# XMICRO-7SEG.net
KiCad netlist of a schematic drawn in EAGLE
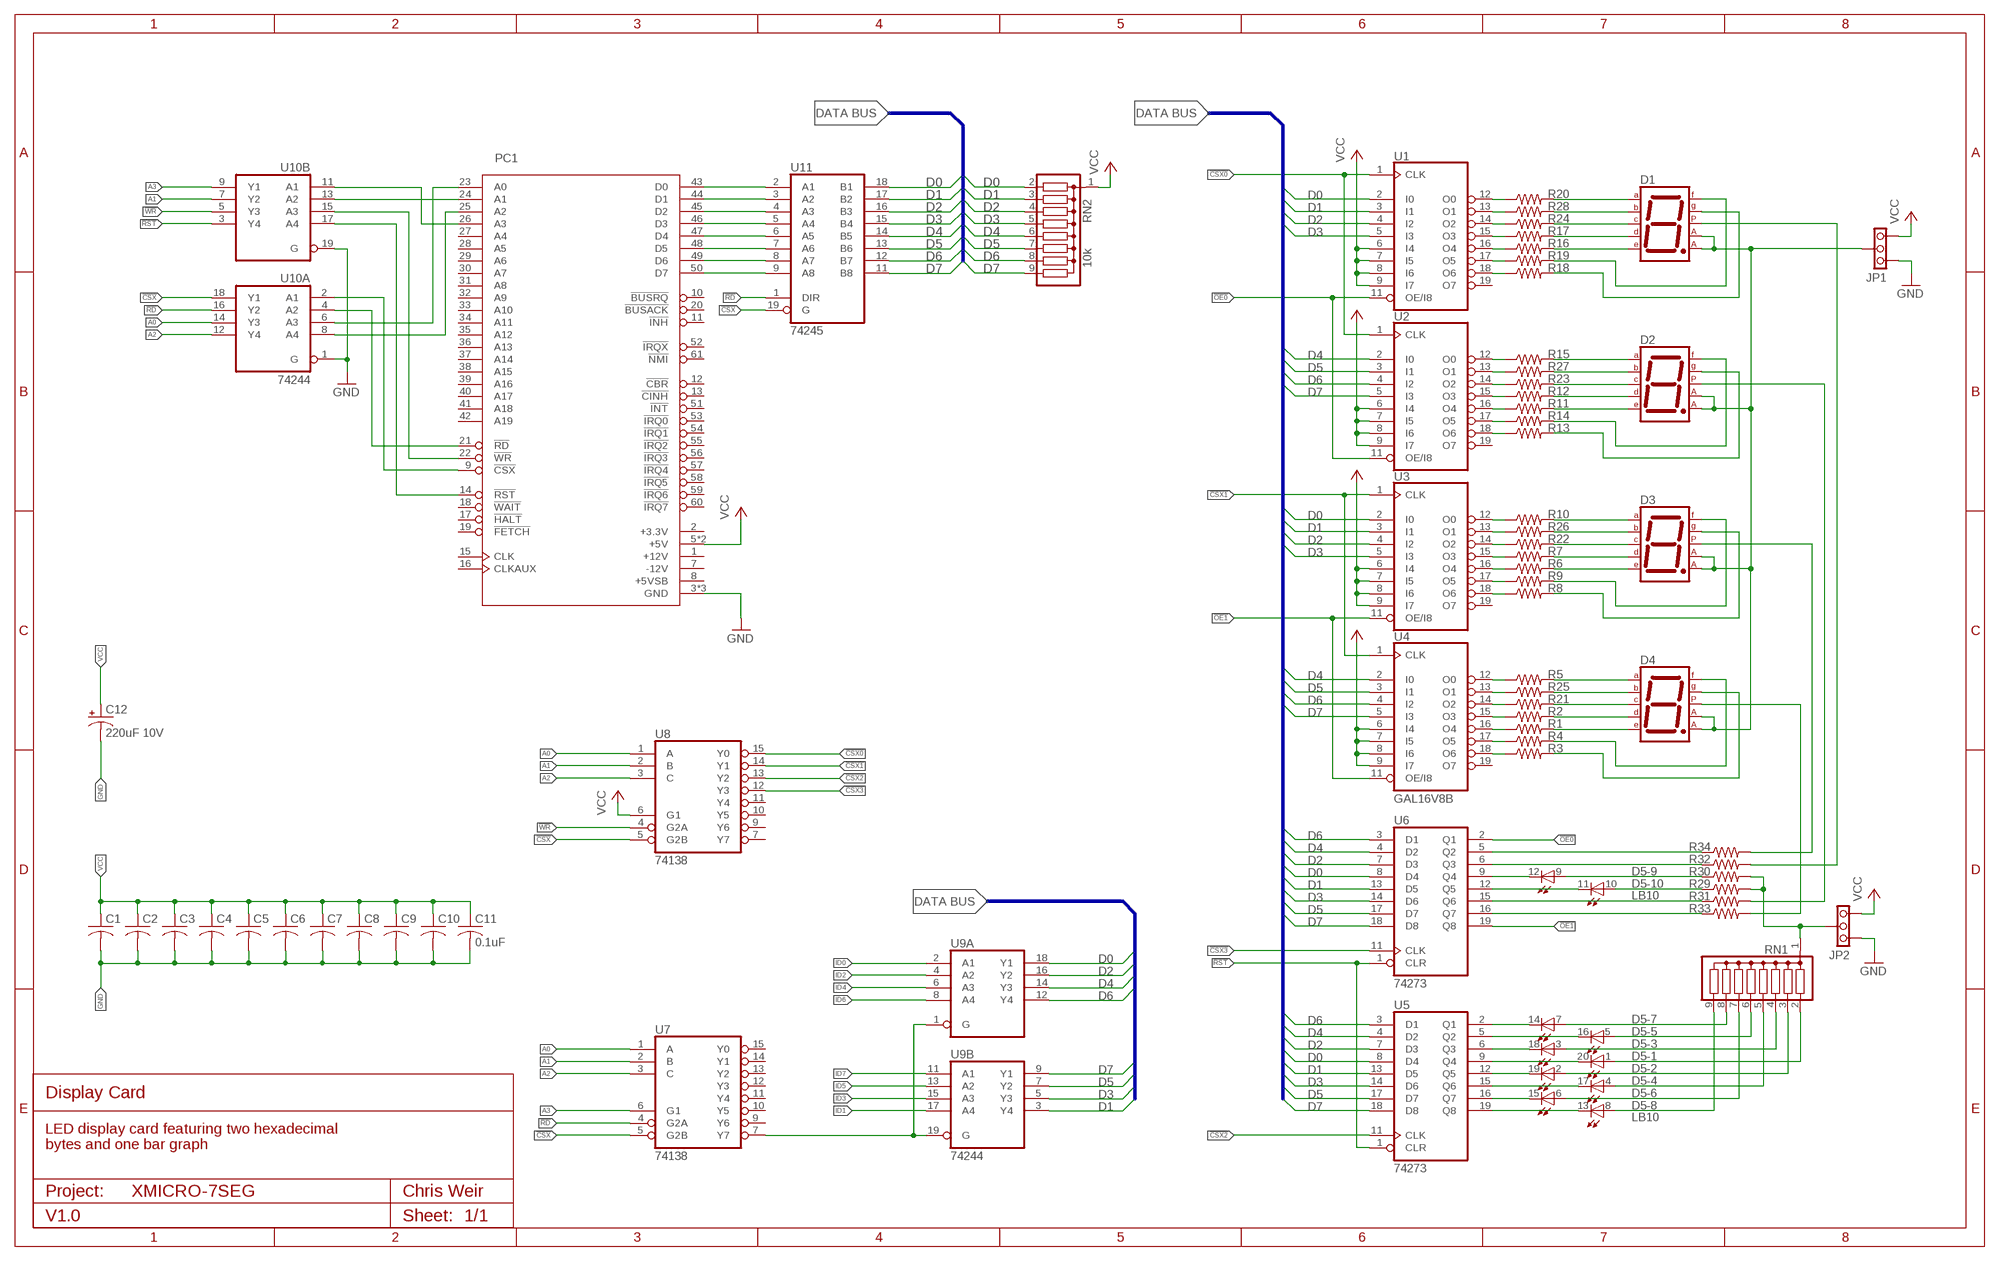
[diagram p0: schematic, sheet 1]

(export (version "E")
  (design (tool "Eeschema 10.0.6"))
  (components
    (comp (ref "C1")
      (value "0.1uF")
      (footprint "eagle-import:C025-024X044")
      (libsource (lib "eagle-import") (part "C-US025-024X044"))
    )
    (comp (ref "C2")
      (value "0.1uF")
      (footprint "eagle-import:C025-024X044")
      (libsource (lib "eagle-import") (part "C-US025-024X044"))
    )
    (comp (ref "C3")
      (value "0.1uF")
      (footprint "eagle-import:C025-024X044")
      (libsource (lib "eagle-import") (part "C-US025-024X044"))
    )
    (comp (ref "C4")
      (value "0.1uF")
      (footprint "eagle-import:C025-024X044")
      (libsource (lib "eagle-import") (part "C-US025-024X044"))
    )
    (comp (ref "C5")
      (value "0.1uF")
      (footprint "eagle-import:C025-024X044")
      (libsource (lib "eagle-import") (part "C-US025-024X044"))
    )
    (comp (ref "C6")
      (value "0.1uF")
      (footprint "eagle-import:C025-024X044")
      (libsource (lib "eagle-import") (part "C-US025-024X044"))
    )
    (comp (ref "C7")
      (value "0.1uF")
      (footprint "eagle-import:C025-024X044")
      (libsource (lib "eagle-import") (part "C-US025-024X044"))
    )
    (comp (ref "C8")
      (value "0.1uF")
      (footprint "eagle-import:C025-024X044")
      (libsource (lib "eagle-import") (part "C-US025-024X044"))
    )
    (comp (ref "C9")
      (value "0.1uF")
      (footprint "eagle-import:C025-024X044")
      (libsource (lib "eagle-import") (part "C-US025-024X044"))
    )
    (comp (ref "C10")
      (value "0.1uF")
      (footprint "eagle-import:C025-024X044")
      (libsource (lib "eagle-import") (part "C-US025-024X044"))
    )
    (comp (ref "C11")
      (value "0.1uF")
      (footprint "eagle-import:C025-024X044")
      (libsource (lib "eagle-import") (part "C-US025-024X044"))
    )
    (comp (ref "C12")
      (value "220uF 10V")
      (footprint "eagle-import:C-10-5")
      (libsource (lib "eagle-import") (part "CPOL-US-10-5"))
    )
    (comp (ref "D1")
      (value "7SEG-CA")
      (footprint "eagle-import:7SEG-13")
      (libsource (lib "eagle-import") (part "7SEG-CA"))
    )
    (comp (ref "D2")
      (value "7SEG-CA")
      (footprint "eagle-import:7SEG-13")
      (libsource (lib "eagle-import") (part "7SEG-CA"))
    )
    (comp (ref "D3")
      (value "7SEG-CA")
      (footprint "eagle-import:7SEG-13")
      (libsource (lib "eagle-import") (part "7SEG-CA"))
    )
    (comp (ref "D4")
      (value "7SEG-CA")
      (footprint "eagle-import:7SEG-13")
      (libsource (lib "eagle-import") (part "7SEG-CA"))
    )
    (comp (ref "D5")
      (value "LB10")
      (footprint "eagle-import:LB10")
      (libsource (lib "eagle-import") (part "LB10"))
    )
    (comp (ref "JP1")
      (value "PINHD1X3THRU")
      (footprint "eagle-import:1X03")
      (libsource (lib "eagle-import") (part "PINHD1X3THRU"))
    )
    (comp (ref "JP2")
      (value "PINHD1X3THRU")
      (footprint "eagle-import:1X03")
      (libsource (lib "eagle-import") (part "PINHD1X3THRU"))
    )
    (comp (ref "PC1")
      (value "XMICRO-BUS-EDGE62M")
      (footprint "eagle-import:EDGE62M")
      (libsource (lib "eagle-import") (part "XMICRO-BUS-EDGE62M"))
    )
    (comp (ref "R1")
      (value "R-US_0207/10")
      (footprint "eagle-import:0207_10")
      (libsource (lib "eagle-import") (part "R-US_0207/10"))
    )
    (comp (ref "R2")
      (value "R-US_0207/10")
      (footprint "eagle-import:0207_10")
      (libsource (lib "eagle-import") (part "R-US_0207/10"))
    )
    (comp (ref "R3")
      (value "R-US_0207/10")
      (footprint "eagle-import:0207_10")
      (libsource (lib "eagle-import") (part "R-US_0207/10"))
    )
    (comp (ref "R4")
      (value "R-US_0207/10")
      (footprint "eagle-import:0207_10")
      (libsource (lib "eagle-import") (part "R-US_0207/10"))
    )
    (comp (ref "R5")
      (value "R-US_0207/10")
      (footprint "eagle-import:0207_10")
      (libsource (lib "eagle-import") (part "R-US_0207/10"))
    )
    (comp (ref "R6")
      (value "R-US_0207/10")
      (footprint "eagle-import:0207_10")
      (libsource (lib "eagle-import") (part "R-US_0207/10"))
    )
    (comp (ref "R7")
      (value "R-US_0207/10")
      (footprint "eagle-import:0207_10")
      (libsource (lib "eagle-import") (part "R-US_0207/10"))
    )
    (comp (ref "R8")
      (value "R-US_0207/10")
      (footprint "eagle-import:0207_10")
      (libsource (lib "eagle-import") (part "R-US_0207/10"))
    )
    (comp (ref "R9")
      (value "R-US_0207/10")
      (footprint "eagle-import:0207_10")
      (libsource (lib "eagle-import") (part "R-US_0207/10"))
    )
    (comp (ref "R10")
      (value "R-US_0207/10")
      (footprint "eagle-import:0207_10")
      (libsource (lib "eagle-import") (part "R-US_0207/10"))
    )
    (comp (ref "R11")
      (value "R-US_0207/10")
      (footprint "eagle-import:0207_10")
      (libsource (lib "eagle-import") (part "R-US_0207/10"))
    )
    (comp (ref "R12")
      (value "R-US_0207/10")
      (footprint "eagle-import:0207_10")
      (libsource (lib "eagle-import") (part "R-US_0207/10"))
    )
    (comp (ref "R13")
      (value "R-US_0207/10")
      (footprint "eagle-import:0207_10")
      (libsource (lib "eagle-import") (part "R-US_0207/10"))
    )
    (comp (ref "R14")
      (value "R-US_0207/10")
      (footprint "eagle-import:0207_10")
      (libsource (lib "eagle-import") (part "R-US_0207/10"))
    )
    (comp (ref "R15")
      (value "R-US_0207/10")
      (footprint "eagle-import:0207_10")
      (libsource (lib "eagle-import") (part "R-US_0207/10"))
    )
    (comp (ref "R16")
      (value "R-US_0207/10")
      (footprint "eagle-import:0207_10")
      (libsource (lib "eagle-import") (part "R-US_0207/10"))
    )
    (comp (ref "R17")
      (value "R-US_0207/10")
      (footprint "eagle-import:0207_10")
      (libsource (lib "eagle-import") (part "R-US_0207/10"))
    )
    (comp (ref "R18")
      (value "R-US_0207/10")
      (footprint "eagle-import:0207_10")
      (libsource (lib "eagle-import") (part "R-US_0207/10"))
    )
    (comp (ref "R19")
      (value "R-US_0207/10")
      (footprint "eagle-import:0207_10")
      (libsource (lib "eagle-import") (part "R-US_0207/10"))
    )
    (comp (ref "R20")
      (value "R-US_0207/10")
      (footprint "eagle-import:0207_10")
      (libsource (lib "eagle-import") (part "R-US_0207/10"))
    )
    (comp (ref "R21")
      (value "R-US_0207/10")
      (footprint "eagle-import:0207_10")
      (libsource (lib "eagle-import") (part "R-US_0207/10"))
    )
    (comp (ref "R22")
      (value "R-US_0207/10")
      (footprint "eagle-import:0207_10")
      (libsource (lib "eagle-import") (part "R-US_0207/10"))
    )
    (comp (ref "R23")
      (value "R-US_0207/10")
      (footprint "eagle-import:0207_10")
      (libsource (lib "eagle-import") (part "R-US_0207/10"))
    )
    (comp (ref "R24")
      (value "R-US_0207/10")
      (footprint "eagle-import:0207_10")
      (libsource (lib "eagle-import") (part "R-US_0207/10"))
    )
    (comp (ref "R25")
      (value "R-US_0207/10")
      (footprint "eagle-import:0207_10")
      (libsource (lib "eagle-import") (part "R-US_0207/10"))
    )
    (comp (ref "R26")
      (value "R-US_0207/10")
      (footprint "eagle-import:0207_10")
      (libsource (lib "eagle-import") (part "R-US_0207/10"))
    )
    (comp (ref "R27")
      (value "R-US_0207/10")
      (footprint "eagle-import:0207_10")
      (libsource (lib "eagle-import") (part "R-US_0207/10"))
    )
    (comp (ref "R28")
      (value "R-US_0207/10")
      (footprint "eagle-import:0207_10")
      (libsource (lib "eagle-import") (part "R-US_0207/10"))
    )
    (comp (ref "R29")
      (value "R-US_0207/10")
      (footprint "eagle-import:0207_10")
      (libsource (lib "eagle-import") (part "R-US_0207/10"))
    )
    (comp (ref "R30")
      (value "R-US_0207/10")
      (footprint "eagle-import:0207_10")
      (libsource (lib "eagle-import") (part "R-US_0207/10"))
    )
    (comp (ref "R31")
      (value "R-US_0207/10")
      (footprint "eagle-import:0207_10")
      (libsource (lib "eagle-import") (part "R-US_0207/10"))
    )
    (comp (ref "R32")
      (value "R-US_0207/10")
      (footprint "eagle-import:0207_10")
      (libsource (lib "eagle-import") (part "R-US_0207/10"))
    )
    (comp (ref "R33")
      (value "R-US_0207/10")
      (footprint "eagle-import:0207_10")
      (libsource (lib "eagle-import") (part "R-US_0207/10"))
    )
    (comp (ref "R34")
      (value "R-US_0207/10")
      (footprint "eagle-import:0207_10")
      (libsource (lib "eagle-import") (part "R-US_0207/10"))
    )
    (comp (ref "RN1")
      (value "G08R")
      (footprint "eagle-import:SIL9")
      (libsource (lib "eagle-import") (part "G08R"))
    )
    (comp (ref "RN2")
      (value "10k")
      (footprint "eagle-import:SIL9")
      (fields (field (name "OC_FARNELL") "unknown") (field (name "OC_NEWARK") "unknown"))
      (libsource (lib "eagle-import") (part "G08R"))
    )
    (comp (ref "U1")
      (value "GAL16V8B")
      (footprint "eagle-import:DIL20")
      (fields (field (name "MPN") "GAL16V8D-7LPN"))
      (libsource (lib "eagle-import") (part "16V8"))
    )
    (comp (ref "U2")
      (value "GAL16V8B")
      (footprint "eagle-import:DIL20")
      (fields (field (name "MPN") "GAL16V8D-7LPN"))
      (libsource (lib "eagle-import") (part "16V8"))
    )
    (comp (ref "U3")
      (value "GAL16V8B")
      (footprint "eagle-import:DIL20")
      (fields (field (name "MPN") "GAL16V8D-7LPN"))
      (libsource (lib "eagle-import") (part "16V8"))
    )
    (comp (ref "U4")
      (value "GAL16V8B")
      (footprint "eagle-import:DIL20")
      (fields (field (name "MPN") "GAL16V8D-7LPN"))
      (libsource (lib "eagle-import") (part "16V8"))
    )
    (comp (ref "U5")
      (value "74273")
      (footprint "eagle-import:DIL20")
      (libsource (lib "eagle-import") (part "74273N"))
    )
    (comp (ref "U6")
      (value "74273")
      (footprint "eagle-import:DIL20")
      (libsource (lib "eagle-import") (part "74273N"))
    )
    (comp (ref "U7")
      (value "74138")
      (footprint "eagle-import:DIL16")
      (libsource (lib "eagle-import") (part "74138NLS"))
    )
    (comp (ref "U8")
      (value "74138")
      (footprint "eagle-import:DIL16")
      (libsource (lib "eagle-import") (part "74138NLS"))
    )
    (comp (ref "U9")
      (value "74244")
      (footprint "eagle-import:DIL20")
      (libsource (lib "eagle-import") (part "74244NLS"))
    )
    (comp (ref "U10")
      (value "74244")
      (footprint "eagle-import:DIL20")
      (libsource (lib "eagle-import") (part "74244NLS"))
    )
    (comp (ref "U11")
      (value "74245")
      (footprint "eagle-import:DIL20")
      (libsource (lib "eagle-import") (part "74245NLS"))
    )
  )
  (nets
    (net (code "1") (name "/D0") (class "Default")
      (node (ref "RN2") (pin "2") (pinfunction "2_2") (pintype "passive"))
      (node (ref "U1") (pin "2") (pinfunction "I0_2") (pintype "input"))
      (node (ref "U11") (pin "18") (pinfunction "B1_18") (pintype "bidirectional"))
      (node (ref "U3") (pin "2") (pinfunction "I0_2") (pintype "input"))
      (node (ref "U5") (pin "8") (pinfunction "D4_8") (pintype "input"))
      (node (ref "U6") (pin "8") (pinfunction "D4_8") (pintype "input"))
      (node (ref "U9") (pin "18") (pinfunction "Y1_18") (pintype "tri_state"))
    )
    (net (code "2") (name "/D1") (class "Default")
      (node (ref "RN2") (pin "3") (pinfunction "3_3") (pintype "passive"))
      (node (ref "U1") (pin "3") (pinfunction "I1_3") (pintype "input"))
      (node (ref "U11") (pin "17") (pinfunction "B2_17") (pintype "bidirectional"))
      (node (ref "U3") (pin "3") (pinfunction "I1_3") (pintype "input"))
      (node (ref "U5") (pin "13") (pinfunction "D5_13") (pintype "input"))
      (node (ref "U6") (pin "13") (pinfunction "D5_13") (pintype "input"))
      (node (ref "U9") (pin "3") (pinfunction "Y4_3") (pintype "tri_state"))
    )
    (net (code "3") (name "/D2") (class "Default")
      (node (ref "RN2") (pin "4") (pinfunction "4_4") (pintype "passive"))
      (node (ref "U1") (pin "4") (pinfunction "I2_4") (pintype "input"))
      (node (ref "U11") (pin "16") (pinfunction "B3_16") (pintype "bidirectional"))
      (node (ref "U3") (pin "4") (pinfunction "I2_4") (pintype "input"))
      (node (ref "U5") (pin "7") (pinfunction "D3_7") (pintype "input"))
      (node (ref "U6") (pin "7") (pinfunction "D3_7") (pintype "input"))
      (node (ref "U9") (pin "16") (pinfunction "Y2_16") (pintype "tri_state"))
    )
    (net (code "4") (name "/D3") (class "Default")
      (node (ref "RN2") (pin "5") (pinfunction "5_5") (pintype "passive"))
      (node (ref "U1") (pin "5") (pinfunction "I3_5") (pintype "input"))
      (node (ref "U11") (pin "15") (pinfunction "B4_15") (pintype "bidirectional"))
      (node (ref "U3") (pin "5") (pinfunction "I3_5") (pintype "input"))
      (node (ref "U5") (pin "14") (pinfunction "D6_14") (pintype "input"))
      (node (ref "U6") (pin "14") (pinfunction "D6_14") (pintype "input"))
      (node (ref "U9") (pin "5") (pinfunction "Y3_5") (pintype "tri_state"))
    )
    (net (code "5") (name "/D4") (class "Default")
      (node (ref "RN2") (pin "6") (pinfunction "6_6") (pintype "passive"))
      (node (ref "U11") (pin "14") (pinfunction "B5_14") (pintype "bidirectional"))
      (node (ref "U2") (pin "2") (pinfunction "I0_2") (pintype "input"))
      (node (ref "U4") (pin "2") (pinfunction "I0_2") (pintype "input"))
      (node (ref "U5") (pin "4") (pinfunction "D2_4") (pintype "input"))
      (node (ref "U6") (pin "4") (pinfunction "D2_4") (pintype "input"))
      (node (ref "U9") (pin "14") (pinfunction "Y3_14") (pintype "tri_state"))
    )
    (net (code "6") (name "/D5") (class "Default")
      (node (ref "RN2") (pin "7") (pinfunction "7_7") (pintype "passive"))
      (node (ref "U11") (pin "13") (pinfunction "B6_13") (pintype "bidirectional"))
      (node (ref "U2") (pin "3") (pinfunction "I1_3") (pintype "input"))
      (node (ref "U4") (pin "3") (pinfunction "I1_3") (pintype "input"))
      (node (ref "U5") (pin "17") (pinfunction "D7_17") (pintype "input"))
      (node (ref "U6") (pin "17") (pinfunction "D7_17") (pintype "input"))
      (node (ref "U9") (pin "7") (pinfunction "Y2_7") (pintype "tri_state"))
    )
    (net (code "7") (name "/D6") (class "Default")
      (node (ref "RN2") (pin "8") (pinfunction "8_8") (pintype "passive"))
      (node (ref "U11") (pin "12") (pinfunction "B7_12") (pintype "bidirectional"))
      (node (ref "U2") (pin "4") (pinfunction "I2_4") (pintype "input"))
      (node (ref "U4") (pin "4") (pinfunction "I2_4") (pintype "input"))
      (node (ref "U5") (pin "3") (pinfunction "D1_3") (pintype "input"))
      (node (ref "U6") (pin "3") (pinfunction "D1_3") (pintype "input"))
      (node (ref "U9") (pin "12") (pinfunction "Y4_12") (pintype "tri_state"))
    )
    (net (code "8") (name "/D7") (class "Default")
      (node (ref "RN2") (pin "9") (pinfunction "9_9") (pintype "passive"))
      (node (ref "U11") (pin "11") (pinfunction "B8_11") (pintype "bidirectional"))
      (node (ref "U2") (pin "5") (pinfunction "I3_5") (pintype "input"))
      (node (ref "U4") (pin "5") (pinfunction "I3_5") (pintype "input"))
      (node (ref "U5") (pin "18") (pinfunction "D8_18") (pintype "input"))
      (node (ref "U6") (pin "18") (pinfunction "D8_18") (pintype "input"))
      (node (ref "U9") (pin "9") (pinfunction "Y1_9") (pintype "tri_state"))
    )
    (net (code "10") (name "/~{CSX0}") (class "Default")
      (node (ref "U1") (pin "1") (pinfunction "CLK_1") (pintype "input"))
      (node (ref "U2") (pin "1") (pinfunction "CLK_1") (pintype "input"))
      (node (ref "U8") (pin "15") (pinfunction "Y0_15") (pintype "output"))
    )
    (net (code "11") (name "/~{CSX1}") (class "Default")
      (node (ref "U3") (pin "1") (pinfunction "CLK_1") (pintype "input"))
      (node (ref "U4") (pin "1") (pinfunction "CLK_1") (pintype "input"))
      (node (ref "U8") (pin "14") (pinfunction "Y1_14") (pintype "output"))
    )
    (net (code "12") (name "/~{CSX2}") (class "Default")
      (node (ref "U5") (pin "11") (pinfunction "CLK_11") (pintype "input"))
      (node (ref "U8") (pin "13") (pinfunction "Y2_13") (pintype "output"))
    )
    (net (code "13") (name "/~{CSX3}") (class "Default")
      (node (ref "U6") (pin "11") (pinfunction "CLK_11") (pintype "input"))
      (node (ref "U8") (pin "12") (pinfunction "Y3_12") (pintype "output"))
    )
    (net (code "14") (name "/~{CSX}") (class "Default")
      (node (ref "U10") (pin "18") (pinfunction "Y1_18") (pintype "tri_state"))
      (node (ref "U11") (pin "19") (pinfunction "G_19") (pintype "input"))
      (node (ref "U7") (pin "5") (pinfunction "G2B_5") (pintype "input"))
      (node (ref "U8") (pin "5") (pinfunction "G2B_5") (pintype "input"))
    )
    (net (code "15") (name "/~{OE0}") (class "Default")
      (node (ref "U1") (pin "11") (pinfunction "OE/I8_11") (pintype "input"))
      (node (ref "U2") (pin "11") (pinfunction "OE/I8_11") (pintype "input"))
      (node (ref "U6") (pin "2") (pinfunction "Q1_2") (pintype "output"))
    )
    (net (code "16") (name "/~{OE1}") (class "Default")
      (node (ref "U3") (pin "11") (pinfunction "OE/I8_11") (pintype "input"))
      (node (ref "U4") (pin "11") (pinfunction "OE/I8_11") (pintype "input"))
      (node (ref "U6") (pin "19") (pinfunction "Q8_19") (pintype "output"))
    )
    (net (code "17") (name "/~{RD}") (class "Default")
      (node (ref "U10") (pin "16") (pinfunction "Y2_16") (pintype "tri_state"))
      (node (ref "U11") (pin "1") (pinfunction "DIR_1") (pintype "input"))
      (node (ref "U7") (pin "4") (pinfunction "G2A_4") (pintype "input"))
    )
    (net (code "18") (name "/~{RST}") (class "Default")
      (node (ref "U10") (pin "3") (pinfunction "Y4_3") (pintype "tri_state"))
      (node (ref "U5") (pin "1") (pinfunction "CLR_1") (pintype "input"))
      (node (ref "U6") (pin "1") (pinfunction "CLR_1") (pintype "input"))
    )
    (net (code "19") (name "/~{WR}") (class "Default")
      (node (ref "U10") (pin "5") (pinfunction "Y3_5") (pintype "tri_state"))
      (node (ref "U8") (pin "4") (pinfunction "G2A_4") (pintype "input"))
    )
    (net (code "20") (name "A0") (class "Default")
      (node (ref "U10") (pin "14") (pinfunction "Y3_14") (pintype "tri_state"))
      (node (ref "U7") (pin "1") (pinfunction "A_1") (pintype "input"))
      (node (ref "U8") (pin "1") (pinfunction "A_1") (pintype "input"))
    )
    (net (code "21") (name "A1") (class "Default")
      (node (ref "U10") (pin "7") (pinfunction "Y2_7") (pintype "tri_state"))
      (node (ref "U7") (pin "2") (pinfunction "B_2") (pintype "input"))
      (node (ref "U8") (pin "2") (pinfunction "B_2") (pintype "input"))
    )
    (net (code "22") (name "A2") (class "Default")
      (node (ref "U10") (pin "12") (pinfunction "Y4_12") (pintype "tri_state"))
      (node (ref "U7") (pin "3") (pinfunction "C_3") (pintype "input"))
      (node (ref "U8") (pin "3") (pinfunction "C_3") (pintype "input"))
    )
    (net (code "23") (name "A3") (class "Default")
      (node (ref "U10") (pin "9") (pinfunction "Y1_9") (pintype "tri_state"))
      (node (ref "U7") (pin "6") (pinfunction "G1_6") (pintype "input"))
    )
    (net (code "24") (name "GND") (class "Default")
      (node (ref "C1") (pin "2") (pinfunction "2_2") (pintype "passive"))
      (node (ref "C10") (pin "2") (pinfunction "2_2") (pintype "passive"))
      (node (ref "C11") (pin "2") (pinfunction "2_2") (pintype "passive"))
      (node (ref "C12") (pin "-") (pinfunction "-_-") (pintype "passive"))
      (node (ref "C2") (pin "2") (pinfunction "2_2") (pintype "passive"))
      (node (ref "C3") (pin "2") (pinfunction "2_2") (pintype "passive"))
      (node (ref "C4") (pin "2") (pinfunction "2_2") (pintype "passive"))
      (node (ref "C5") (pin "2") (pinfunction "2_2") (pintype "passive"))
      (node (ref "C6") (pin "2") (pinfunction "2_2") (pintype "passive"))
      (node (ref "C7") (pin "2") (pinfunction "2_2") (pintype "passive"))
      (node (ref "C8") (pin "2") (pinfunction "2_2") (pintype "passive"))
      (node (ref "C9") (pin "2") (pinfunction "2_2") (pintype "passive"))
      (node (ref "JP1") (pin "1") (pinfunction "1_1") (pintype "passive"))
      (node (ref "JP2") (pin "1") (pinfunction "1_1") (pintype "passive"))
      (node (ref "PC1") (pin "3") (pinfunction "GND_3") (pintype "bidirectional"))
      (node (ref "PC1") (pin "4") (pinfunction "GND_4") (pintype "bidirectional"))
      (node (ref "PC1") (pin "62") (pinfunction "GND_62") (pintype "bidirectional"))
      (node (ref "U10") (pin "1") (pinfunction "G_1") (pintype "input"))
      (node (ref "U10") (pin "19") (pinfunction "G_19") (pintype "input"))
    )
    (net (code "25") (name "ID0") (class "Default")
      (node (ref "U9") (pin "2") (pinfunction "A1_2") (pintype "input"))
    )
    (net (code "26") (name "ID1") (class "Default")
      (node (ref "U9") (pin "17") (pinfunction "A4_17") (pintype "input"))
    )
    (net (code "27") (name "ID2") (class "Default")
      (node (ref "U9") (pin "4") (pinfunction "A2_4") (pintype "input"))
    )
    (net (code "28") (name "ID3") (class "Default")
      (node (ref "U9") (pin "15") (pinfunction "A3_15") (pintype "input"))
    )
    (net (code "29") (name "ID4") (class "Default")
      (node (ref "U9") (pin "6") (pinfunction "A3_6") (pintype "input"))
    )
    (net (code "30") (name "ID5") (class "Default")
      (node (ref "U9") (pin "13") (pinfunction "A2_13") (pintype "input"))
    )
    (net (code "31") (name "ID6") (class "Default")
      (node (ref "U9") (pin "8") (pinfunction "A4_8") (pintype "input"))
    )
    (net (code "32") (name "ID7") (class "Default")
      (node (ref "U9") (pin "11") (pinfunction "A1_11") (pintype "input"))
    )
    (net (code "33") (name "Net-(D1-A)") (class "Default")
      (node (ref "D1") (pin "7") (pinfunction "A_7") (pintype "passive"))
      (node (ref "R20") (pin "2") (pinfunction "2_2") (pintype "passive"))
    )
    (net (code "34") (name "Net-(D1-B)") (class "Default")
      (node (ref "D1") (pin "6") (pinfunction "B_6") (pintype "passive"))
      (node (ref "R28") (pin "2") (pinfunction "2_2") (pintype "passive"))
    )
    (net (code "35") (name "Net-(D1-C)") (class "Default")
      (node (ref "D1") (pin "4") (pinfunction "C_4") (pintype "passive"))
      (node (ref "R24") (pin "2") (pinfunction "2_2") (pintype "passive"))
    )
    (net (code "36") (name "Net-(D1-CA1)") (class "Default")
      (node (ref "D1") (pin "3") (pinfunction "CA1_3") (pintype "passive"))
      (node (ref "D1") (pin "8") (pinfunction "CA2_8") (pintype "passive"))
      (node (ref "D2") (pin "3") (pinfunction "CA1_3") (pintype "passive"))
      (node (ref "D2") (pin "8") (pinfunction "CA2_8") (pintype "passive"))
      (node (ref "D3") (pin "3") (pinfunction "CA1_3") (pintype "passive"))
      (node (ref "D3") (pin "8") (pinfunction "CA2_8") (pintype "passive"))
      (node (ref "D4") (pin "3") (pinfunction "CA1_3") (pintype "passive"))
      (node (ref "D4") (pin "8") (pinfunction "CA2_8") (pintype "passive"))
      (node (ref "JP1") (pin "2") (pinfunction "2_2") (pintype "passive"))
    )
    (net (code "37") (name "Net-(D1-D)") (class "Default")
      (node (ref "D1") (pin "2") (pinfunction "D_2") (pintype "passive"))
      (node (ref "R17") (pin "2") (pinfunction "2_2") (pintype "passive"))
    )
    (net (code "38") (name "Net-(D1-DP)") (class "Default")
      (node (ref "D1") (pin "5") (pinfunction "DP_5") (pintype "passive"))
      (node (ref "R32") (pin "2") (pinfunction "2_2") (pintype "passive"))
    )
    (net (code "39") (name "Net-(D1-E)") (class "Default")
      (node (ref "D1") (pin "1") (pinfunction "E_1") (pintype "passive"))
      (node (ref "R16") (pin "2") (pinfunction "2_2") (pintype "passive"))
    )
    (net (code "40") (name "Net-(D1-F)") (class "Default")
      (node (ref "D1") (pin "9") (pinfunction "F_9") (pintype "passive"))
      (node (ref "R19") (pin "2") (pinfunction "2_2") (pintype "passive"))
    )
    (net (code "41") (name "Net-(D1-G)") (class "Default")
      (node (ref "D1") (pin "10") (pinfunction "G_10") (pintype "passive"))
      (node (ref "R18") (pin "2") (pinfunction "2_2") (pintype "passive"))
    )
    (net (code "42") (name "Net-(D2-A)") (class "Default")
      (node (ref "D2") (pin "7") (pinfunction "A_7") (pintype "passive"))
      (node (ref "R15") (pin "2") (pinfunction "2_2") (pintype "passive"))
    )
    (net (code "43") (name "Net-(D2-B)") (class "Default")
      (node (ref "D2") (pin "6") (pinfunction "B_6") (pintype "passive"))
      (node (ref "R27") (pin "2") (pinfunction "2_2") (pintype "passive"))
    )
    (net (code "44") (name "Net-(D2-C)") (class "Default")
      (node (ref "D2") (pin "4") (pinfunction "C_4") (pintype "passive"))
      (node (ref "R23") (pin "2") (pinfunction "2_2") (pintype "passive"))
    )
    (net (code "45") (name "Net-(D2-D)") (class "Default")
      (node (ref "D2") (pin "2") (pinfunction "D_2") (pintype "passive"))
      (node (ref "R12") (pin "2") (pinfunction "2_2") (pintype "passive"))
    )
    (net (code "46") (name "Net-(D2-DP)") (class "Default")
      (node (ref "D2") (pin "5") (pinfunction "DP_5") (pintype "passive"))
      (node (ref "R31") (pin "2") (pinfunction "2_2") (pintype "passive"))
    )
    (net (code "47") (name "Net-(D2-E)") (class "Default")
      (node (ref "D2") (pin "1") (pinfunction "E_1") (pintype "passive"))
      (node (ref "R11") (pin "2") (pinfunction "2_2") (pintype "passive"))
    )
    (net (code "48") (name "Net-(D2-F)") (class "Default")
      (node (ref "D2") (pin "9") (pinfunction "F_9") (pintype "passive"))
      (node (ref "R14") (pin "2") (pinfunction "2_2") (pintype "passive"))
    )
    (net (code "49") (name "Net-(D2-G)") (class "Default")
      (node (ref "D2") (pin "10") (pinfunction "G_10") (pintype "passive"))
      (node (ref "R13") (pin "2") (pinfunction "2_2") (pintype "passive"))
    )
    (net (code "50") (name "Net-(D3-A)") (class "Default")
      (node (ref "D3") (pin "7") (pinfunction "A_7") (pintype "passive"))
      (node (ref "R10") (pin "2") (pinfunction "2_2") (pintype "passive"))
    )
    (net (code "51") (name "Net-(D3-B)") (class "Default")
      (node (ref "D3") (pin "6") (pinfunction "B_6") (pintype "passive"))
      (node (ref "R26") (pin "2") (pinfunction "2_2") (pintype "passive"))
    )
    (net (code "52") (name "Net-(D3-C)") (class "Default")
      (node (ref "D3") (pin "4") (pinfunction "C_4") (pintype "passive"))
      (node (ref "R22") (pin "2") (pinfunction "2_2") (pintype "passive"))
    )
    (net (code "53") (name "Net-(D3-D)") (class "Default")
      (node (ref "D3") (pin "2") (pinfunction "D_2") (pintype "passive"))
      (node (ref "R7") (pin "2") (pinfunction "2_2") (pintype "passive"))
    )
    (net (code "54") (name "Net-(D3-DP)") (class "Default")
      (node (ref "D3") (pin "5") (pinfunction "DP_5") (pintype "passive"))
      (node (ref "R34") (pin "2") (pinfunction "2_2") (pintype "passive"))
    )
    (net (code "55") (name "Net-(D3-E)") (class "Default")
      (node (ref "D3") (pin "1") (pinfunction "E_1") (pintype "passive"))
      (node (ref "R6") (pin "2") (pinfunction "2_2") (pintype "passive"))
    )
    (net (code "56") (name "Net-(D3-F)") (class "Default")
      (node (ref "D3") (pin "9") (pinfunction "F_9") (pintype "passive"))
      (node (ref "R9") (pin "2") (pinfunction "2_2") (pintype "passive"))
    )
    (net (code "57") (name "Net-(D3-G)") (class "Default")
      (node (ref "D3") (pin "10") (pinfunction "G_10") (pintype "passive"))
      (node (ref "R8") (pin "2") (pinfunction "2_2") (pintype "passive"))
    )
    (net (code "58") (name "Net-(D4-A)") (class "Default")
      (node (ref "D4") (pin "7") (pinfunction "A_7") (pintype "passive"))
      (node (ref "R5") (pin "2") (pinfunction "2_2") (pintype "passive"))
    )
    (net (code "59") (name "Net-(D4-B)") (class "Default")
      (node (ref "D4") (pin "6") (pinfunction "B_6") (pintype "passive"))
      (node (ref "R25") (pin "2") (pinfunction "2_2") (pintype "passive"))
    )
    (net (code "60") (name "Net-(D4-C)") (class "Default")
      (node (ref "D4") (pin "4") (pinfunction "C_4") (pintype "passive"))
      (node (ref "R21") (pin "2") (pinfunction "2_2") (pintype "passive"))
    )
    (net (code "61") (name "Net-(D4-D)") (class "Default")
      (node (ref "D4") (pin "2") (pinfunction "D_2") (pintype "passive"))
      (node (ref "R2") (pin "2") (pinfunction "2_2") (pintype "passive"))
    )
    (net (code "62") (name "Net-(D4-DP)") (class "Default")
      (node (ref "D4") (pin "5") (pinfunction "DP_5") (pintype "passive"))
      (node (ref "R33") (pin "2") (pinfunction "2_2") (pintype "passive"))
    )
    (net (code "63") (name "Net-(D4-E)") (class "Default")
      (node (ref "D4") (pin "1") (pinfunction "E_1") (pintype "passive"))
      (node (ref "R1") (pin "2") (pinfunction "2_2") (pintype "passive"))
    )
    (net (code "64") (name "Net-(D4-F)") (class "Default")
      (node (ref "D4") (pin "9") (pinfunction "F_9") (pintype "passive"))
      (node (ref "R4") (pin "2") (pinfunction "2_2") (pintype "passive"))
    )
    (net (code "65") (name "Net-(D4-G)") (class "Default")
      (node (ref "D4") (pin "10") (pinfunction "G_10") (pintype "passive"))
      (node (ref "R3") (pin "2") (pinfunction "2_2") (pintype "passive"))
    )
    (net (code "66") (name "Net-(D5A-A)") (class "Default")
      (node (ref "D5") (pin "1") (pinfunction "A_1") (pintype "passive"))
      (node (ref "RN1") (pin "2") (pinfunction "2_2") (pintype "passive"))
    )
    (net (code "67") (name "Net-(D5A-C)") (class "Default")
      (node (ref "D5") (pin "20") (pinfunction "C_20") (pintype "passive"))
      (node (ref "U5") (pin "9") (pinfunction "Q4_9") (pintype "output"))
    )
    (net (code "68") (name "Net-(D5B-A)") (class "Default")
      (node (ref "D5") (pin "10") (pinfunction "A_10") (pintype "passive"))
      (node (ref "R29") (pin "1") (pinfunction "1_1") (pintype "passive"))
    )
    (net (code "69") (name "Net-(D5B-C)") (class "Default")
      (node (ref "D5") (pin "11") (pinfunction "C_11") (pintype "passive"))
      (node (ref "U6") (pin "12") (pinfunction "Q5_12") (pintype "output"))
    )
    (net (code "70") (name "Net-(D5C-A)") (class "Default")
      (node (ref "D5") (pin "2") (pinfunction "A_2") (pintype "passive"))
      (node (ref "RN1") (pin "3") (pinfunction "3_3") (pintype "passive"))
    )
    (net (code "71") (name "Net-(D5C-C)") (class "Default")
      (node (ref "D5") (pin "19") (pinfunction "C_19") (pintype "passive"))
      (node (ref "U5") (pin "12") (pinfunction "Q5_12") (pintype "output"))
    )
    (net (code "72") (name "Net-(D5D-A)") (class "Default")
      (node (ref "D5") (pin "3") (pinfunction "A_3") (pintype "passive"))
      (node (ref "RN1") (pin "4") (pinfunction "4_4") (pintype "passive"))
    )
    (net (code "73") (name "Net-(D5D-C)") (class "Default")
      (node (ref "D5") (pin "18") (pinfunction "C_18") (pintype "passive"))
      (node (ref "U5") (pin "6") (pinfunction "Q3_6") (pintype "output"))
    )
    (net (code "74") (name "Net-(D5E-A)") (class "Default")
      (node (ref "D5") (pin "4") (pinfunction "A_4") (pintype "passive"))
      (node (ref "RN1") (pin "5") (pinfunction "5_5") (pintype "passive"))
    )
    (net (code "75") (name "Net-(D5E-C)") (class "Default")
      (node (ref "D5") (pin "17") (pinfunction "C_17") (pintype "passive"))
      (node (ref "U5") (pin "15") (pinfunction "Q6_15") (pintype "output"))
    )
    (net (code "76") (name "Net-(D5F-A)") (class "Default")
      (node (ref "D5") (pin "5") (pinfunction "A_5") (pintype "passive"))
      (node (ref "RN1") (pin "6") (pinfunction "6_6") (pintype "passive"))
    )
    (net (code "77") (name "Net-(D5F-C)") (class "Default")
      (node (ref "D5") (pin "16") (pinfunction "C_16") (pintype "passive"))
      (node (ref "U5") (pin "5") (pinfunction "Q2_5") (pintype "output"))
    )
    (net (code "78") (name "Net-(D5G-A)") (class "Default")
      (node (ref "D5") (pin "6") (pinfunction "A_6") (pintype "passive"))
      (node (ref "RN1") (pin "7") (pinfunction "7_7") (pintype "passive"))
    )
    (net (code "79") (name "Net-(D5G-C)") (class "Default")
      (node (ref "D5") (pin "15") (pinfunction "C_15") (pintype "passive"))
      (node (ref "U5") (pin "16") (pinfunction "Q7_16") (pintype "output"))
    )
    (net (code "80") (name "Net-(D5H-A)") (class "Default")
      (node (ref "D5") (pin "7") (pinfunction "A_7") (pintype "passive"))
      (node (ref "RN1") (pin "8") (pinfunction "8_8") (pintype "passive"))
    )
    (net (code "81") (name "Net-(D5H-C)") (class "Default")
      (node (ref "D5") (pin "14") (pinfunction "C_14") (pintype "passive"))
      (node (ref "U5") (pin "2") (pinfunction "Q1_2") (pintype "output"))
    )
    (net (code "82") (name "Net-(D5I-A)") (class "Default")
      (node (ref "D5") (pin "8") (pinfunction "A_8") (pintype "passive"))
      (node (ref "RN1") (pin "9") (pinfunction "9_9") (pintype "passive"))
    )
    (net (code "83") (name "Net-(D5I-C)") (class "Default")
      (node (ref "D5") (pin "13") (pinfunction "C_13") (pintype "passive"))
      (node (ref "U5") (pin "19") (pinfunction "Q8_19") (pintype "output"))
    )
    (net (code "84") (name "Net-(D5J-A)") (class "Default")
      (node (ref "D5") (pin "9") (pinfunction "A_9") (pintype "passive"))
      (node (ref "R30") (pin "1") (pinfunction "1_1") (pintype "passive"))
    )
    (net (code "85") (name "Net-(D5J-C)") (class "Default")
      (node (ref "D5") (pin "12") (pinfunction "C_12") (pintype "passive"))
      (node (ref "U6") (pin "9") (pinfunction "Q4_9") (pintype "output"))
    )
    (net (code "86") (name "Net-(JP2-Pad2)") (class "Default")
      (node (ref "JP2") (pin "2") (pinfunction "2_2") (pintype "passive"))
      (node (ref "R29") (pin "2") (pinfunction "2_2") (pintype "passive"))
      (node (ref "R30") (pin "2") (pinfunction "2_2") (pintype "passive"))
      (node (ref "RN1") (pin "1") (pinfunction "1_1") (pintype "passive"))
    )
    (net (code "87") (name "Net-(PC1-A0)") (class "Default")
      (node (ref "PC1") (pin "23") (pinfunction "A0_23") (pintype "bidirectional"))
      (node (ref "U10") (pin "6") (pinfunction "A3_6") (pintype "input"))
    )
    (net (code "88") (name "Net-(PC1-A1)") (class "Default")
      (node (ref "PC1") (pin "24") (pinfunction "A1_24") (pintype "bidirectional"))
      (node (ref "U10") (pin "13") (pinfunction "A2_13") (pintype "input"))
    )
    (net (code "89") (name "Net-(PC1-A2)") (class "Default")
      (node (ref "PC1") (pin "25") (pinfunction "A2_25") (pintype "bidirectional"))
      (node (ref "U10") (pin "8") (pinfunction "A4_8") (pintype "input"))
    )
    (net (code "90") (name "Net-(PC1-A3)") (class "Default")
      (node (ref "PC1") (pin "26") (pinfunction "A3_26") (pintype "bidirectional"))
      (node (ref "U10") (pin "11") (pinfunction "A1_11") (pintype "input"))
    )
    (net (code "91") (name "Net-(PC1-D0)") (class "Default")
      (node (ref "PC1") (pin "43") (pinfunction "D0_43") (pintype "bidirectional"))
      (node (ref "U11") (pin "2") (pinfunction "A1_2") (pintype "bidirectional"))
    )
    (net (code "92") (name "Net-(PC1-D1)") (class "Default")
      (node (ref "PC1") (pin "44") (pinfunction "D1_44") (pintype "bidirectional"))
      (node (ref "U11") (pin "3") (pinfunction "A2_3") (pintype "bidirectional"))
    )
    (net (code "93") (name "Net-(PC1-D2)") (class "Default")
      (node (ref "PC1") (pin "45") (pinfunction "D2_45") (pintype "bidirectional"))
      (node (ref "U11") (pin "4") (pinfunction "A3_4") (pintype "bidirectional"))
    )
    (net (code "94") (name "Net-(PC1-D3)") (class "Default")
      (node (ref "PC1") (pin "46") (pinfunction "D3_46") (pintype "bidirectional"))
      (node (ref "U11") (pin "5") (pinfunction "A4_5") (pintype "bidirectional"))
    )
    (net (code "95") (name "Net-(PC1-D4)") (class "Default")
      (node (ref "PC1") (pin "47") (pinfunction "D4_47") (pintype "bidirectional"))
      (node (ref "U11") (pin "6") (pinfunction "A5_6") (pintype "bidirectional"))
    )
    (net (code "96") (name "Net-(PC1-D5)") (class "Default")
      (node (ref "PC1") (pin "48") (pinfunction "D5_48") (pintype "bidirectional"))
      (node (ref "U11") (pin "7") (pinfunction "A6_7") (pintype "bidirectional"))
    )
    (net (code "97") (name "Net-(PC1-D6)") (class "Default")
      (node (ref "PC1") (pin "49") (pinfunction "D6_49") (pintype "bidirectional"))
      (node (ref "U11") (pin "8") (pinfunction "A7_8") (pintype "bidirectional"))
    )
    (net (code "98") (name "Net-(PC1-D7)") (class "Default")
      (node (ref "PC1") (pin "50") (pinfunction "D7_50") (pintype "bidirectional"))
      (node (ref "U11") (pin "9") (pinfunction "A8_9") (pintype "bidirectional"))
    )
    (net (code "99") (name "Net-(PC1-~{CSX})") (class "Default")
      (node (ref "PC1") (pin "9") (pinfunction "~{CSX}_9") (pintype "bidirectional"))
      (node (ref "U10") (pin "2") (pinfunction "A1_2") (pintype "input"))
    )
    (net (code "100") (name "Net-(PC1-~{RD})") (class "Default")
      (node (ref "PC1") (pin "21") (pinfunction "~{RD}_21") (pintype "bidirectional"))
      (node (ref "U10") (pin "4") (pinfunction "A2_4") (pintype "input"))
    )
    (net (code "101") (name "Net-(PC1-~{RST})") (class "Default")
      (node (ref "PC1") (pin "14") (pinfunction "~{RST}_14") (pintype "bidirectional"))
      (node (ref "U10") (pin "17") (pinfunction "A4_17") (pintype "input"))
    )
    (net (code "102") (name "Net-(PC1-~{WR})") (class "Default")
      (node (ref "PC1") (pin "22") (pinfunction "~{WR}_22") (pintype "bidirectional"))
      (node (ref "U10") (pin "15") (pinfunction "A3_15") (pintype "input"))
    )
    (net (code "103") (name "Net-(U1A-O0)") (class "Default")
      (node (ref "R20") (pin "1") (pinfunction "1_1") (pintype "passive"))
      (node (ref "U1") (pin "12") (pinfunction "O0_12") (pintype "bidirectional"))
    )
    (net (code "104") (name "Net-(U1A-O1)") (class "Default")
      (node (ref "R28") (pin "1") (pinfunction "1_1") (pintype "passive"))
      (node (ref "U1") (pin "13") (pinfunction "O1_13") (pintype "bidirectional"))
    )
    (net (code "105") (name "Net-(U1A-O2)") (class "Default")
      (node (ref "R24") (pin "1") (pinfunction "1_1") (pintype "passive"))
      (node (ref "U1") (pin "14") (pinfunction "O2_14") (pintype "bidirectional"))
    )
    (net (code "106") (name "Net-(U1A-O3)") (class "Default")
      (node (ref "R17") (pin "1") (pinfunction "1_1") (pintype "passive"))
      (node (ref "U1") (pin "15") (pinfunction "O3_15") (pintype "bidirectional"))
    )
    (net (code "107") (name "Net-(U1A-O4)") (class "Default")
      (node (ref "R16") (pin "1") (pinfunction "1_1") (pintype "passive"))
      (node (ref "U1") (pin "16") (pinfunction "O4_16") (pintype "bidirectional"))
    )
    (net (code "108") (name "Net-(U1A-O5)") (class "Default")
      (node (ref "R19") (pin "1") (pinfunction "1_1") (pintype "passive"))
      (node (ref "U1") (pin "17") (pinfunction "O5_17") (pintype "bidirectional"))
    )
    (net (code "109") (name "Net-(U1A-O6)") (class "Default")
      (node (ref "R18") (pin "1") (pinfunction "1_1") (pintype "passive"))
      (node (ref "U1") (pin "18") (pinfunction "O6_18") (pintype "bidirectional"))
    )
    (net (code "110") (name "Net-(U2A-O0)") (class "Default")
      (node (ref "R15") (pin "1") (pinfunction "1_1") (pintype "passive"))
      (node (ref "U2") (pin "12") (pinfunction "O0_12") (pintype "bidirectional"))
    )
    (net (code "111") (name "Net-(U2A-O1)") (class "Default")
      (node (ref "R27") (pin "1") (pinfunction "1_1") (pintype "passive"))
      (node (ref "U2") (pin "13") (pinfunction "O1_13") (pintype "bidirectional"))
    )
    (net (code "112") (name "Net-(U2A-O2)") (class "Default")
      (node (ref "R23") (pin "1") (pinfunction "1_1") (pintype "passive"))
      (node (ref "U2") (pin "14") (pinfunction "O2_14") (pintype "bidirectional"))
    )
    (net (code "113") (name "Net-(U2A-O3)") (class "Default")
      (node (ref "R12") (pin "1") (pinfunction "1_1") (pintype "passive"))
      (node (ref "U2") (pin "15") (pinfunction "O3_15") (pintype "bidirectional"))
    )
    (net (code "114") (name "Net-(U2A-O4)") (class "Default")
      (node (ref "R11") (pin "1") (pinfunction "1_1") (pintype "passive"))
      (node (ref "U2") (pin "16") (pinfunction "O4_16") (pintype "bidirectional"))
    )
    (net (code "115") (name "Net-(U2A-O5)") (class "Default")
      (node (ref "R14") (pin "1") (pinfunction "1_1") (pintype "passive"))
      (node (ref "U2") (pin "17") (pinfunction "O5_17") (pintype "bidirectional"))
    )
    (net (code "116") (name "Net-(U2A-O6)") (class "Default")
      (node (ref "R13") (pin "1") (pinfunction "1_1") (pintype "passive"))
      (node (ref "U2") (pin "18") (pinfunction "O6_18") (pintype "bidirectional"))
    )
    (net (code "117") (name "Net-(U3A-O0)") (class "Default")
      (node (ref "R10") (pin "1") (pinfunction "1_1") (pintype "passive"))
      (node (ref "U3") (pin "12") (pinfunction "O0_12") (pintype "bidirectional"))
    )
    (net (code "118") (name "Net-(U3A-O1)") (class "Default")
      (node (ref "R26") (pin "1") (pinfunction "1_1") (pintype "passive"))
      (node (ref "U3") (pin "13") (pinfunction "O1_13") (pintype "bidirectional"))
    )
    (net (code "119") (name "Net-(U3A-O2)") (class "Default")
      (node (ref "R22") (pin "1") (pinfunction "1_1") (pintype "passive"))
      (node (ref "U3") (pin "14") (pinfunction "O2_14") (pintype "bidirectional"))
    )
    (net (code "120") (name "Net-(U3A-O3)") (class "Default")
      (node (ref "R7") (pin "1") (pinfunction "1_1") (pintype "passive"))
      (node (ref "U3") (pin "15") (pinfunction "O3_15") (pintype "bidirectional"))
    )
    (net (code "121") (name "Net-(U3A-O4)") (class "Default")
      (node (ref "R6") (pin "1") (pinfunction "1_1") (pintype "passive"))
      (node (ref "U3") (pin "16") (pinfunction "O4_16") (pintype "bidirectional"))
    )
    (net (code "122") (name "Net-(U3A-O5)") (class "Default")
      (node (ref "R9") (pin "1") (pinfunction "1_1") (pintype "passive"))
      (node (ref "U3") (pin "17") (pinfunction "O5_17") (pintype "bidirectional"))
    )
    (net (code "123") (name "Net-(U3A-O6)") (class "Default")
      (node (ref "R8") (pin "1") (pinfunction "1_1") (pintype "passive"))
      (node (ref "U3") (pin "18") (pinfunction "O6_18") (pintype "bidirectional"))
    )
    (net (code "124") (name "Net-(U4A-O0)") (class "Default")
      (node (ref "R5") (pin "1") (pinfunction "1_1") (pintype "passive"))
      (node (ref "U4") (pin "12") (pinfunction "O0_12") (pintype "bidirectional"))
    )
    (net (code "125") (name "Net-(U4A-O1)") (class "Default")
      (node (ref "R25") (pin "1") (pinfunction "1_1") (pintype "passive"))
      (node (ref "U4") (pin "13") (pinfunction "O1_13") (pintype "bidirectional"))
    )
    (net (code "126") (name "Net-(U4A-O2)") (class "Default")
      (node (ref "R21") (pin "1") (pinfunction "1_1") (pintype "passive"))
      (node (ref "U4") (pin "14") (pinfunction "O2_14") (pintype "bidirectional"))
    )
    (net (code "127") (name "Net-(U4A-O3)") (class "Default")
      (node (ref "R2") (pin "1") (pinfunction "1_1") (pintype "passive"))
      (node (ref "U4") (pin "15") (pinfunction "O3_15") (pintype "bidirectional"))
    )
    (net (code "128") (name "Net-(U4A-O4)") (class "Default")
      (node (ref "R1") (pin "1") (pinfunction "1_1") (pintype "passive"))
      (node (ref "U4") (pin "16") (pinfunction "O4_16") (pintype "bidirectional"))
    )
    (net (code "129") (name "Net-(U4A-O5)") (class "Default")
      (node (ref "R4") (pin "1") (pinfunction "1_1") (pintype "passive"))
      (node (ref "U4") (pin "17") (pinfunction "O5_17") (pintype "bidirectional"))
    )
    (net (code "130") (name "Net-(U4A-O6)") (class "Default")
      (node (ref "R3") (pin "1") (pinfunction "1_1") (pintype "passive"))
      (node (ref "U4") (pin "18") (pinfunction "O6_18") (pintype "bidirectional"))
    )
    (net (code "131") (name "Net-(U6A-Q2)") (class "Default")
      (node (ref "R34") (pin "1") (pinfunction "1_1") (pintype "passive"))
      (node (ref "U6") (pin "5") (pinfunction "Q2_5") (pintype "output"))
    )
    (net (code "132") (name "Net-(U6A-Q3)") (class "Default")
      (node (ref "R32") (pin "1") (pinfunction "1_1") (pintype "passive"))
      (node (ref "U6") (pin "6") (pinfunction "Q3_6") (pintype "output"))
    )
    (net (code "133") (name "Net-(U6A-Q6)") (class "Default")
      (node (ref "R31") (pin "1") (pinfunction "1_1") (pintype "passive"))
      (node (ref "U6") (pin "15") (pinfunction "Q6_15") (pintype "output"))
    )
    (net (code "134") (name "Net-(U6A-Q7)") (class "Default")
      (node (ref "R33") (pin "1") (pinfunction "1_1") (pintype "passive"))
      (node (ref "U6") (pin "16") (pinfunction "Q7_16") (pintype "output"))
    )
    (net (code "135") (name "Net-(U7A-Y7)") (class "Default")
      (node (ref "U7") (pin "7") (pinfunction "Y7_7") (pintype "output"))
      (node (ref "U9") (pin "1") (pinfunction "G_1") (pintype "input"))
      (node (ref "U9") (pin "19") (pinfunction "G_19") (pintype "input"))
    )
    (net (code "136") (name "VCC") (class "Default")
      (node (ref "C1") (pin "1") (pinfunction "1_1") (pintype "passive"))
      (node (ref "C10") (pin "1") (pinfunction "1_1") (pintype "passive"))
      (node (ref "C11") (pin "1") (pinfunction "1_1") (pintype "passive"))
      (node (ref "C12") (pin "+") (pinfunction "+_+") (pintype "passive"))
      (node (ref "C2") (pin "1") (pinfunction "1_1") (pintype "passive"))
      (node (ref "C3") (pin "1") (pinfunction "1_1") (pintype "passive"))
      (node (ref "C4") (pin "1") (pinfunction "1_1") (pintype "passive"))
      (node (ref "C5") (pin "1") (pinfunction "1_1") (pintype "passive"))
      (node (ref "C6") (pin "1") (pinfunction "1_1") (pintype "passive"))
      (node (ref "C7") (pin "1") (pinfunction "1_1") (pintype "passive"))
      (node (ref "C8") (pin "1") (pinfunction "1_1") (pintype "passive"))
      (node (ref "C9") (pin "1") (pinfunction "1_1") (pintype "passive"))
      (node (ref "JP1") (pin "3") (pinfunction "3_3") (pintype "passive"))
      (node (ref "JP2") (pin "3") (pinfunction "3_3") (pintype "passive"))
      (node (ref "PC1") (pin "5") (pinfunction "+5V_5") (pintype "bidirectional"))
      (node (ref "PC1") (pin "6") (pinfunction "+5V_6") (pintype "bidirectional"))
      (node (ref "RN2") (pin "1") (pinfunction "1_1") (pintype "passive"))
      (node (ref "U1") (pin "6") (pinfunction "I4_6") (pintype "input"))
      (node (ref "U1") (pin "7") (pinfunction "I5_7") (pintype "input"))
      (node (ref "U1") (pin "8") (pinfunction "I6_8") (pintype "input"))
      (node (ref "U1") (pin "9") (pinfunction "I7_9") (pintype "input"))
      (node (ref "U2") (pin "6") (pinfunction "I4_6") (pintype "input"))
      (node (ref "U2") (pin "7") (pinfunction "I5_7") (pintype "input"))
      (node (ref "U2") (pin "8") (pinfunction "I6_8") (pintype "input"))
      (node (ref "U2") (pin "9") (pinfunction "I7_9") (pintype "input"))
      (node (ref "U3") (pin "6") (pinfunction "I4_6") (pintype "input"))
      (node (ref "U3") (pin "7") (pinfunction "I5_7") (pintype "input"))
      (node (ref "U3") (pin "8") (pinfunction "I6_8") (pintype "input"))
      (node (ref "U3") (pin "9") (pinfunction "I7_9") (pintype "input"))
      (node (ref "U4") (pin "6") (pinfunction "I4_6") (pintype "input"))
      (node (ref "U4") (pin "7") (pinfunction "I5_7") (pintype "input"))
      (node (ref "U4") (pin "8") (pinfunction "I6_8") (pintype "input"))
      (node (ref "U4") (pin "9") (pinfunction "I7_9") (pintype "input"))
      (node (ref "U8") (pin "6") (pinfunction "G1_6") (pintype "input"))
    )
    (net (code "137") (name "unconnected-(PC1-+3.3V-Pad2)") (class "Default")
      (node (ref "PC1") (pin "2") (pinfunction "+3.3V_2") (pintype "bidirectional"))
    )
    (net (code "138") (name "unconnected-(PC1-+5VSB-Pad8)") (class "Default")
      (node (ref "PC1") (pin "8") (pinfunction "+5VSB_8") (pintype "bidirectional"))
    )
    (net (code "139") (name "unconnected-(PC1-+12V-Pad1)") (class "Default")
      (node (ref "PC1") (pin "1") (pinfunction "+12V_1") (pintype "bidirectional"))
    )
    (net (code "140") (name "unconnected-(PC1--12V-Pad7)") (class "Default")
      (node (ref "PC1") (pin "7") (pinfunction "-12V_7") (pintype "bidirectional"))
    )
    (net (code "141") (name "unconnected-(PC1-A4-Pad27)") (class "Default")
      (node (ref "PC1") (pin "27") (pinfunction "A4_27") (pintype "bidirectional"))
    )
    (net (code "142") (name "unconnected-(PC1-A5-Pad28)") (class "Default")
      (node (ref "PC1") (pin "28") (pinfunction "A5_28") (pintype "bidirectional"))
    )
    (net (code "143") (name "unconnected-(PC1-A6-Pad29)") (class "Default")
      (node (ref "PC1") (pin "29") (pinfunction "A6_29") (pintype "bidirectional"))
    )
    (net (code "144") (name "unconnected-(PC1-A7-Pad30)") (class "Default")
      (node (ref "PC1") (pin "30") (pinfunction "A7_30") (pintype "bidirectional"))
    )
    (net (code "145") (name "unconnected-(PC1-A8-Pad31)") (class "Default")
      (node (ref "PC1") (pin "31") (pinfunction "A8_31") (pintype "bidirectional"))
    )
    (net (code "146") (name "unconnected-(PC1-A9-Pad32)") (class "Default")
      (node (ref "PC1") (pin "32") (pinfunction "A9_32") (pintype "bidirectional"))
    )
    (net (code "147") (name "unconnected-(PC1-A10-Pad33)") (class "Default")
      (node (ref "PC1") (pin "33") (pinfunction "A10_33") (pintype "bidirectional"))
    )
    (net (code "148") (name "unconnected-(PC1-A11-Pad34)") (class "Default")
      (node (ref "PC1") (pin "34") (pinfunction "A11_34") (pintype "bidirectional"))
    )
    (net (code "149") (name "unconnected-(PC1-A12-Pad35)") (class "Default")
      (node (ref "PC1") (pin "35") (pinfunction "A12_35") (pintype "bidirectional"))
    )
    (net (code "150") (name "unconnected-(PC1-A13-Pad36)") (class "Default")
      (node (ref "PC1") (pin "36") (pinfunction "A13_36") (pintype "bidirectional"))
    )
    (net (code "151") (name "unconnected-(PC1-A14-Pad37)") (class "Default")
      (node (ref "PC1") (pin "37") (pinfunction "A14_37") (pintype "bidirectional"))
    )
    (net (code "152") (name "unconnected-(PC1-A15-Pad38)") (class "Default")
      (node (ref "PC1") (pin "38") (pinfunction "A15_38") (pintype "bidirectional"))
    )
    (net (code "153") (name "unconnected-(PC1-A16-Pad39)") (class "Default")
      (node (ref "PC1") (pin "39") (pinfunction "A16_39") (pintype "bidirectional"))
    )
    (net (code "154") (name "unconnected-(PC1-A17-Pad40)") (class "Default")
      (node (ref "PC1") (pin "40") (pinfunction "A17_40") (pintype "bidirectional"))
    )
    (net (code "155") (name "unconnected-(PC1-A18-Pad41)") (class "Default")
      (node (ref "PC1") (pin "41") (pinfunction "A18_41") (pintype "bidirectional"))
    )
    (net (code "156") (name "unconnected-(PC1-A19-Pad42)") (class "Default")
      (node (ref "PC1") (pin "42") (pinfunction "A19_42") (pintype "bidirectional"))
    )
    (net (code "157") (name "unconnected-(PC1-CLK-Pad15)") (class "Default")
      (node (ref "PC1") (pin "15") (pinfunction "CLK_15") (pintype "bidirectional"))
    )
    (net (code "158") (name "unconnected-(PC1-CLKAUX-Pad16)") (class "Default")
      (node (ref "PC1") (pin "16") (pinfunction "CLKAUX_16") (pintype "bidirectional"))
    )
    (net (code "159") (name "unconnected-(PC1-~{BUSACK}-Pad20)") (class "Default")
      (node (ref "PC1") (pin "20") (pinfunction "~{BUSACK}_20") (pintype "bidirectional"))
    )
    (net (code "160") (name "unconnected-(PC1-~{BUSRQ}-Pad10)") (class "Default")
      (node (ref "PC1") (pin "10") (pinfunction "~{BUSRQ}_10") (pintype "bidirectional"))
    )
    (net (code "161") (name "unconnected-(PC1-~{CBR}-Pad12)") (class "Default")
      (node (ref "PC1") (pin "12") (pinfunction "~{CBR}_12") (pintype "bidirectional"))
    )
    (net (code "162") (name "unconnected-(PC1-~{CINH}-Pad13)") (class "Default")
      (node (ref "PC1") (pin "13") (pinfunction "~{CINH}_13") (pintype "bidirectional"))
    )
    (net (code "163") (name "unconnected-(PC1-~{FETCH}-Pad19)") (class "Default")
      (node (ref "PC1") (pin "19") (pinfunction "~{FETCH}_19") (pintype "bidirectional"))
    )
    (net (code "164") (name "unconnected-(PC1-~{HALT}-Pad17)") (class "Default")
      (node (ref "PC1") (pin "17") (pinfunction "~{HALT}_17") (pintype "bidirectional"))
    )
    (net (code "165") (name "unconnected-(PC1-~{INH}-Pad11)") (class "Default")
      (node (ref "PC1") (pin "11") (pinfunction "~{INH}_11") (pintype "bidirectional"))
    )
    (net (code "166") (name "unconnected-(PC1-~{INT}-Pad51)") (class "Default")
      (node (ref "PC1") (pin "51") (pinfunction "~{INT}_51") (pintype "bidirectional"))
    )
    (net (code "167") (name "unconnected-(PC1-~{IRQ0}-Pad53)") (class "Default")
      (node (ref "PC1") (pin "53") (pinfunction "~{IRQ0}_53") (pintype "bidirectional"))
    )
    (net (code "168") (name "unconnected-(PC1-~{IRQ1}-Pad54)") (class "Default")
      (node (ref "PC1") (pin "54") (pinfunction "~{IRQ1}_54") (pintype "bidirectional"))
    )
    (net (code "169") (name "unconnected-(PC1-~{IRQ2}-Pad55)") (class "Default")
      (node (ref "PC1") (pin "55") (pinfunction "~{IRQ2}_55") (pintype "bidirectional"))
    )
    (net (code "170") (name "unconnected-(PC1-~{IRQ3}-Pad56)") (class "Default")
      (node (ref "PC1") (pin "56") (pinfunction "~{IRQ3}_56") (pintype "bidirectional"))
    )
    (net (code "171") (name "unconnected-(PC1-~{IRQ4}-Pad57)") (class "Default")
      (node (ref "PC1") (pin "57") (pinfunction "~{IRQ4}_57") (pintype "bidirectional"))
    )
    (net (code "172") (name "unconnected-(PC1-~{IRQ5}-Pad58)") (class "Default")
      (node (ref "PC1") (pin "58") (pinfunction "~{IRQ5}_58") (pintype "bidirectional"))
    )
    (net (code "173") (name "unconnected-(PC1-~{IRQ6}-Pad59)") (class "Default")
      (node (ref "PC1") (pin "59") (pinfunction "~{IRQ6}_59") (pintype "bidirectional"))
    )
    (net (code "174") (name "unconnected-(PC1-~{IRQ7}-Pad60)") (class "Default")
      (node (ref "PC1") (pin "60") (pinfunction "~{IRQ7}_60") (pintype "bidirectional"))
    )
    (net (code "175") (name "unconnected-(PC1-~{IRQX}-Pad52)") (class "Default")
      (node (ref "PC1") (pin "52") (pinfunction "~{IRQX}_52") (pintype "bidirectional"))
    )
    (net (code "176") (name "unconnected-(PC1-~{NMI}-Pad61)") (class "Default")
      (node (ref "PC1") (pin "61") (pinfunction "~{NMI}_61") (pintype "bidirectional"))
    )
    (net (code "177") (name "unconnected-(PC1-~{WAIT}-Pad18)") (class "Default")
      (node (ref "PC1") (pin "18") (pinfunction "~{WAIT}_18") (pintype "bidirectional"))
    )
    (net (code "178") (name "unconnected-(U1A-O7-Pad19)") (class "Default")
      (node (ref "U1") (pin "19") (pinfunction "O7_19") (pintype "bidirectional"))
    )
    (net (code "179") (name "unconnected-(U2A-O7-Pad19)") (class "Default")
      (node (ref "U2") (pin "19") (pinfunction "O7_19") (pintype "bidirectional"))
    )
    (net (code "180") (name "unconnected-(U3A-O7-Pad19)") (class "Default")
      (node (ref "U3") (pin "19") (pinfunction "O7_19") (pintype "bidirectional"))
    )
    (net (code "181") (name "unconnected-(U4A-O7-Pad19)") (class "Default")
      (node (ref "U4") (pin "19") (pinfunction "O7_19") (pintype "bidirectional"))
    )
    (net (code "182") (name "unconnected-(U7A-Y0-Pad15)") (class "Default")
      (node (ref "U7") (pin "15") (pinfunction "Y0_15") (pintype "output"))
    )
    (net (code "183") (name "unconnected-(U7A-Y1-Pad14)") (class "Default")
      (node (ref "U7") (pin "14") (pinfunction "Y1_14") (pintype "output"))
    )
    (net (code "184") (name "unconnected-(U7A-Y2-Pad13)") (class "Default")
      (node (ref "U7") (pin "13") (pinfunction "Y2_13") (pintype "output"))
    )
    (net (code "185") (name "unconnected-(U7A-Y3-Pad12)") (class "Default")
      (node (ref "U7") (pin "12") (pinfunction "Y3_12") (pintype "output"))
    )
    (net (code "186") (name "unconnected-(U7A-Y4-Pad11)") (class "Default")
      (node (ref "U7") (pin "11") (pinfunction "Y4_11") (pintype "output"))
    )
    (net (code "187") (name "unconnected-(U7A-Y5-Pad10)") (class "Default")
      (node (ref "U7") (pin "10") (pinfunction "Y5_10") (pintype "output"))
    )
    (net (code "188") (name "unconnected-(U7A-Y6-Pad9)") (class "Default")
      (node (ref "U7") (pin "9") (pinfunction "Y6_9") (pintype "output"))
    )
    (net (code "189") (name "unconnected-(U8A-Y4-Pad11)") (class "Default")
      (node (ref "U8") (pin "11") (pinfunction "Y4_11") (pintype "output"))
    )
    (net (code "190") (name "unconnected-(U8A-Y5-Pad10)") (class "Default")
      (node (ref "U8") (pin "10") (pinfunction "Y5_10") (pintype "output"))
    )
    (net (code "191") (name "unconnected-(U8A-Y6-Pad9)") (class "Default")
      (node (ref "U8") (pin "9") (pinfunction "Y6_9") (pintype "output"))
    )
    (net (code "192") (name "unconnected-(U8A-Y7-Pad7)") (class "Default")
      (node (ref "U8") (pin "7") (pinfunction "Y7_7") (pintype "output"))
    )
  )
)
